# stm32f407ig_breakout.net
KiCad netlist of a schematic drawn in EAGLE
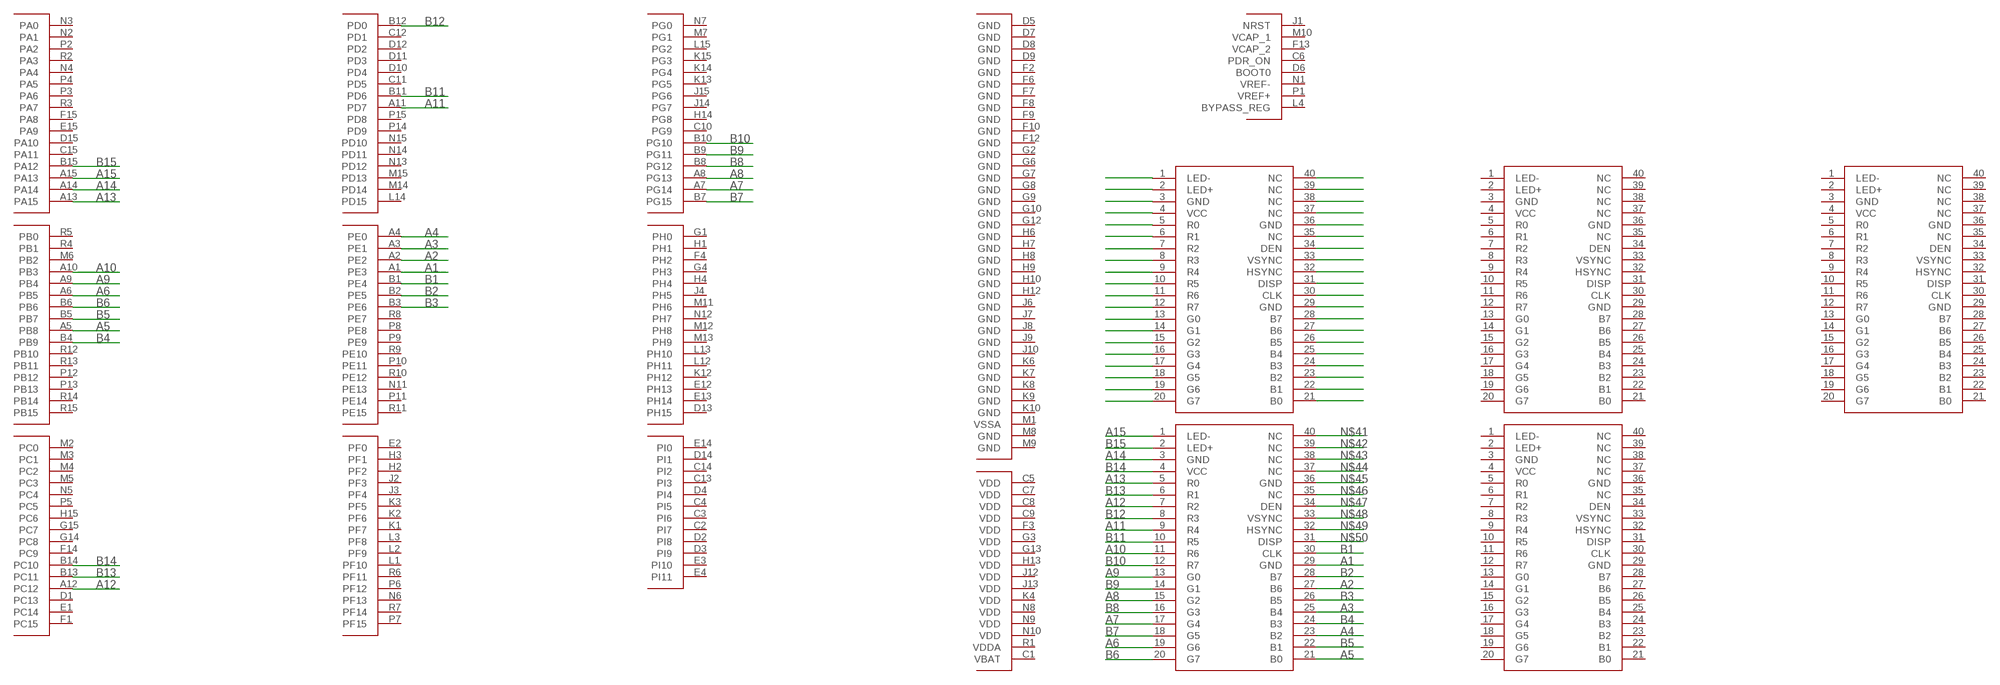
[diagram p0: schematic, sheet 1]

(export (version "E")
  (design (tool "Eeschema 10.0.6"))
  (components
    (comp (ref "TFT1")
      (value "MOLEX_CONNECTORS_SMD_NHD-4.3-480272EF-ATXL")
      (footprint "eagle-import:MOLEX_CONNECTORS_SMD_40-PIN_SMD")
      (libsource (lib "eagle-import") (part "MOLEX_CONNECTORS_SMD_NHD-4.3-480272EF-ATXL"))
    )
    (comp (ref "TFT2")
      (value "MOLEX_CONNECTORS_SMD_NHD-4.3-480272EF-ATXL")
      (footprint "eagle-import:MOLEX_CONNECTORS_SMD_40-PIN_SMD")
      (libsource (lib "eagle-import") (part "MOLEX_CONNECTORS_SMD_NHD-4.3-480272EF-ATXL"))
    )
    (comp (ref "TFT3")
      (value "MOLEX_CONNECTORS_SMD_NHD-4.3-480272EF-ATXL")
      (footprint "eagle-import:MOLEX_CONNECTORS_SMD_40-PIN_SMD")
      (libsource (lib "eagle-import") (part "MOLEX_CONNECTORS_SMD_NHD-4.3-480272EF-ATXL"))
    )
    (comp (ref "TFT4")
      (value "MOLEX_CONNECTORS_SMD_NHD-4.3-480272EF-ATXL")
      (footprint "eagle-import:MOLEX_CONNECTORS_SMD_40-PIN_SMD")
      (libsource (lib "eagle-import") (part "MOLEX_CONNECTORS_SMD_NHD-4.3-480272EF-ATXL"))
    )
    (comp (ref "TFT5")
      (value "MOLEX_CONNECTORS_SMD_NHD-4.3-480272EF-ATXL")
      (footprint "eagle-import:MOLEX_CONNECTORS_SMD_40-PIN_SMD")
      (libsource (lib "eagle-import") (part "MOLEX_CONNECTORS_SMD_NHD-4.3-480272EF-ATXL"))
    )
    (comp (ref "U$1")
      (value "STM32F407IG")
      (footprint "eagle-import:UFBGA176+25")
      (libsource (lib "eagle-import") (part "STM32F407IG"))
    )
  )
  (nets
    (net (code "1") (name "/A1") (class "Default")
      (node (ref "TFT4") (pin "29") (pinfunction "GND_29") (pintype "bidirectional"))
      (node (ref "U$1") (pin "A1") (pinfunction "PE3_A1") (pintype "bidirectional"))
    )
    (net (code "2") (name "/A2") (class "Default")
      (node (ref "TFT4") (pin "27") (pinfunction "B6_27") (pintype "bidirectional"))
      (node (ref "U$1") (pin "A2") (pinfunction "PE2_A2") (pintype "bidirectional"))
    )
    (net (code "3") (name "/A3") (class "Default")
      (node (ref "TFT4") (pin "25") (pinfunction "B4_25") (pintype "bidirectional"))
      (node (ref "U$1") (pin "A3") (pinfunction "PE1_A3") (pintype "bidirectional"))
    )
    (net (code "4") (name "/A4") (class "Default")
      (node (ref "TFT4") (pin "23") (pinfunction "B2_23") (pintype "bidirectional"))
      (node (ref "U$1") (pin "A4") (pinfunction "PE0_A4") (pintype "bidirectional"))
    )
    (net (code "5") (name "/A5") (class "Default")
      (node (ref "TFT4") (pin "21") (pinfunction "B0_21") (pintype "bidirectional"))
      (node (ref "U$1") (pin "A5") (pinfunction "PB8_A5") (pintype "bidirectional"))
    )
    (net (code "6") (name "/A6") (class "Default")
      (node (ref "TFT4") (pin "19") (pinfunction "G6_19") (pintype "bidirectional"))
      (node (ref "U$1") (pin "A6") (pinfunction "PB5_A6") (pintype "bidirectional"))
    )
    (net (code "7") (name "/A7") (class "Default")
      (node (ref "TFT4") (pin "17") (pinfunction "G4_17") (pintype "bidirectional"))
      (node (ref "U$1") (pin "A7") (pinfunction "PG14_A7") (pintype "bidirectional"))
    )
    (net (code "8") (name "/A8") (class "Default")
      (node (ref "TFT4") (pin "15") (pinfunction "G2_15") (pintype "bidirectional"))
      (node (ref "U$1") (pin "A8") (pinfunction "PG13_A8") (pintype "bidirectional"))
    )
    (net (code "9") (name "/A9") (class "Default")
      (node (ref "TFT4") (pin "13") (pinfunction "G0_13") (pintype "bidirectional"))
      (node (ref "U$1") (pin "A9") (pinfunction "PB4_A9") (pintype "bidirectional"))
    )
    (net (code "10") (name "/A10") (class "Default")
      (node (ref "TFT4") (pin "11") (pinfunction "R6_11") (pintype "bidirectional"))
      (node (ref "U$1") (pin "A10") (pinfunction "PB3_A10") (pintype "bidirectional"))
    )
    (net (code "11") (name "/A11") (class "Default")
      (node (ref "TFT4") (pin "9") (pinfunction "R4_9") (pintype "bidirectional"))
      (node (ref "U$1") (pin "A11") (pinfunction "PD7_A11") (pintype "bidirectional"))
    )
    (net (code "12") (name "/A12") (class "Default")
      (node (ref "TFT4") (pin "7") (pinfunction "R2_7") (pintype "bidirectional"))
      (node (ref "U$1") (pin "A12") (pinfunction "PC12_A12") (pintype "bidirectional"))
    )
    (net (code "13") (name "/A13") (class "Default")
      (node (ref "TFT4") (pin "5") (pinfunction "R0_5") (pintype "bidirectional"))
      (node (ref "U$1") (pin "A13") (pinfunction "PA15_A13") (pintype "bidirectional"))
    )
    (net (code "14") (name "/A14") (class "Default")
      (node (ref "TFT4") (pin "3") (pinfunction "GND_3") (pintype "bidirectional"))
      (node (ref "U$1") (pin "A14") (pinfunction "PA14_A14") (pintype "bidirectional"))
    )
    (net (code "15") (name "/A15") (class "Default")
      (node (ref "TFT4") (pin "1") (pinfunction "LED-_1") (pintype "bidirectional"))
      (node (ref "U$1") (pin "A15") (pinfunction "PA13_A15") (pintype "bidirectional"))
    )
    (net (code "16") (name "/B1") (class "Default")
      (node (ref "TFT4") (pin "30") (pinfunction "CLK_30") (pintype "bidirectional"))
      (node (ref "U$1") (pin "B1") (pinfunction "PE4_B1") (pintype "bidirectional"))
    )
    (net (code "17") (name "/B2") (class "Default")
      (node (ref "TFT4") (pin "28") (pinfunction "B7_28") (pintype "bidirectional"))
      (node (ref "U$1") (pin "B2") (pinfunction "PE5_B2") (pintype "bidirectional"))
    )
    (net (code "18") (name "/B3") (class "Default")
      (node (ref "TFT4") (pin "26") (pinfunction "B5_26") (pintype "bidirectional"))
      (node (ref "U$1") (pin "B3") (pinfunction "PE6_B3") (pintype "bidirectional"))
    )
    (net (code "19") (name "/B4") (class "Default")
      (node (ref "TFT4") (pin "24") (pinfunction "B3_24") (pintype "bidirectional"))
      (node (ref "U$1") (pin "B4") (pinfunction "PB9_B4") (pintype "bidirectional"))
    )
    (net (code "20") (name "/B5") (class "Default")
      (node (ref "TFT4") (pin "22") (pinfunction "B1_22") (pintype "bidirectional"))
      (node (ref "U$1") (pin "B5") (pinfunction "PB7_B5") (pintype "bidirectional"))
    )
    (net (code "21") (name "/B6") (class "Default")
      (node (ref "TFT4") (pin "20") (pinfunction "G7_20") (pintype "bidirectional"))
      (node (ref "U$1") (pin "B6") (pinfunction "PB6_B6") (pintype "bidirectional"))
    )
    (net (code "22") (name "/B7") (class "Default")
      (node (ref "TFT4") (pin "18") (pinfunction "G5_18") (pintype "bidirectional"))
      (node (ref "U$1") (pin "B7") (pinfunction "PG15_B7") (pintype "bidirectional"))
    )
    (net (code "23") (name "/B8") (class "Default")
      (node (ref "TFT4") (pin "16") (pinfunction "G3_16") (pintype "bidirectional"))
      (node (ref "U$1") (pin "B8") (pinfunction "PG12_B8") (pintype "bidirectional"))
    )
    (net (code "24") (name "/B9") (class "Default")
      (node (ref "TFT4") (pin "14") (pinfunction "G1_14") (pintype "bidirectional"))
      (node (ref "U$1") (pin "B9") (pinfunction "PG11_B9") (pintype "bidirectional"))
    )
    (net (code "25") (name "/B10") (class "Default")
      (node (ref "TFT4") (pin "12") (pinfunction "R7_12") (pintype "bidirectional"))
      (node (ref "U$1") (pin "B10") (pinfunction "PG10_B10") (pintype "bidirectional"))
    )
    (net (code "26") (name "/B11") (class "Default")
      (node (ref "TFT4") (pin "10") (pinfunction "R5_10") (pintype "bidirectional"))
      (node (ref "U$1") (pin "B11") (pinfunction "PD6_B11") (pintype "bidirectional"))
    )
    (net (code "27") (name "/B12") (class "Default")
      (node (ref "TFT4") (pin "8") (pinfunction "R3_8") (pintype "bidirectional"))
      (node (ref "U$1") (pin "B12") (pinfunction "PD0_B12") (pintype "bidirectional"))
    )
    (net (code "28") (name "/B13") (class "Default")
      (node (ref "TFT4") (pin "6") (pinfunction "R1_6") (pintype "bidirectional"))
      (node (ref "U$1") (pin "B13") (pinfunction "PC11_B13") (pintype "bidirectional"))
    )
    (net (code "29") (name "/B14") (class "Default")
      (node (ref "TFT4") (pin "4") (pinfunction "VCC_4") (pintype "bidirectional"))
      (node (ref "U$1") (pin "B14") (pinfunction "PC10_B14") (pintype "bidirectional"))
    )
    (net (code "30") (name "/B15") (class "Default")
      (node (ref "TFT4") (pin "2") (pinfunction "LED+_2") (pintype "bidirectional"))
      (node (ref "U$1") (pin "B15") (pinfunction "PA12_B15") (pintype "bidirectional"))
    )
    (net (code "31") (name "/N$41") (class "Default")
      (node (ref "TFT4") (pin "40") (pinfunction "NC_40") (pintype "bidirectional"))
    )
    (net (code "32") (name "/N$42") (class "Default")
      (node (ref "TFT4") (pin "39") (pinfunction "NC_39") (pintype "bidirectional"))
    )
    (net (code "33") (name "/N$43") (class "Default")
      (node (ref "TFT4") (pin "38") (pinfunction "NC_38") (pintype "bidirectional"))
    )
    (net (code "34") (name "/N$44") (class "Default")
      (node (ref "TFT4") (pin "37") (pinfunction "NC_37") (pintype "bidirectional"))
    )
    (net (code "35") (name "/N$45") (class "Default")
      (node (ref "TFT4") (pin "36") (pinfunction "GND_36") (pintype "bidirectional"))
    )
    (net (code "36") (name "/N$46") (class "Default")
      (node (ref "TFT4") (pin "35") (pinfunction "NC_35") (pintype "bidirectional"))
    )
    (net (code "37") (name "/N$47") (class "Default")
      (node (ref "TFT4") (pin "34") (pinfunction "DEN_34") (pintype "bidirectional"))
    )
    (net (code "38") (name "/N$48") (class "Default")
      (node (ref "TFT4") (pin "33") (pinfunction "VSYNC_33") (pintype "bidirectional"))
    )
    (net (code "39") (name "/N$49") (class "Default")
      (node (ref "TFT4") (pin "32") (pinfunction "HSYNC_32") (pintype "bidirectional"))
    )
    (net (code "40") (name "/N$50") (class "Default")
      (node (ref "TFT4") (pin "31") (pinfunction "DISP_31") (pintype "bidirectional"))
    )
    (net (code "41") (name "unconnected-(TFT1-B0-Pad21)") (class "Default")
      (node (ref "TFT1") (pin "21") (pinfunction "B0_21") (pintype "bidirectional"))
    )
    (net (code "42") (name "unconnected-(TFT1-B1-Pad22)") (class "Default")
      (node (ref "TFT1") (pin "22") (pinfunction "B1_22") (pintype "bidirectional"))
    )
    (net (code "43") (name "unconnected-(TFT1-B2-Pad23)") (class "Default")
      (node (ref "TFT1") (pin "23") (pinfunction "B2_23") (pintype "bidirectional"))
    )
    (net (code "44") (name "unconnected-(TFT1-B3-Pad24)") (class "Default")
      (node (ref "TFT1") (pin "24") (pinfunction "B3_24") (pintype "bidirectional"))
    )
    (net (code "45") (name "unconnected-(TFT1-B4-Pad25)") (class "Default")
      (node (ref "TFT1") (pin "25") (pinfunction "B4_25") (pintype "bidirectional"))
    )
    (net (code "46") (name "unconnected-(TFT1-B5-Pad26)") (class "Default")
      (node (ref "TFT1") (pin "26") (pinfunction "B5_26") (pintype "bidirectional"))
    )
    (net (code "47") (name "unconnected-(TFT1-B6-Pad27)") (class "Default")
      (node (ref "TFT1") (pin "27") (pinfunction "B6_27") (pintype "bidirectional"))
    )
    (net (code "48") (name "unconnected-(TFT1-B7-Pad28)") (class "Default")
      (node (ref "TFT1") (pin "28") (pinfunction "B7_28") (pintype "bidirectional"))
    )
    (net (code "49") (name "unconnected-(TFT1-CLK-Pad30)") (class "Default")
      (node (ref "TFT1") (pin "30") (pinfunction "CLK_30") (pintype "bidirectional"))
    )
    (net (code "50") (name "unconnected-(TFT1-DEN-Pad34)") (class "Default")
      (node (ref "TFT1") (pin "34") (pinfunction "DEN_34") (pintype "bidirectional"))
    )
    (net (code "51") (name "unconnected-(TFT1-DISP-Pad31)") (class "Default")
      (node (ref "TFT1") (pin "31") (pinfunction "DISP_31") (pintype "bidirectional"))
    )
    (net (code "52") (name "unconnected-(TFT1-G0-Pad13)") (class "Default")
      (node (ref "TFT1") (pin "13") (pinfunction "G0_13") (pintype "bidirectional"))
    )
    (net (code "53") (name "unconnected-(TFT1-G1-Pad14)") (class "Default")
      (node (ref "TFT1") (pin "14") (pinfunction "G1_14") (pintype "bidirectional"))
    )
    (net (code "54") (name "unconnected-(TFT1-G2-Pad15)") (class "Default")
      (node (ref "TFT1") (pin "15") (pinfunction "G2_15") (pintype "bidirectional"))
    )
    (net (code "55") (name "unconnected-(TFT1-G3-Pad16)") (class "Default")
      (node (ref "TFT1") (pin "16") (pinfunction "G3_16") (pintype "bidirectional"))
    )
    (net (code "56") (name "unconnected-(TFT1-G4-Pad17)") (class "Default")
      (node (ref "TFT1") (pin "17") (pinfunction "G4_17") (pintype "bidirectional"))
    )
    (net (code "57") (name "unconnected-(TFT1-G5-Pad18)") (class "Default")
      (node (ref "TFT1") (pin "18") (pinfunction "G5_18") (pintype "bidirectional"))
    )
    (net (code "58") (name "unconnected-(TFT1-G6-Pad19)") (class "Default")
      (node (ref "TFT1") (pin "19") (pinfunction "G6_19") (pintype "bidirectional"))
    )
    (net (code "59") (name "unconnected-(TFT1-G7-Pad20)") (class "Default")
      (node (ref "TFT1") (pin "20") (pinfunction "G7_20") (pintype "bidirectional"))
    )
    (net (code "60") (name "unconnected-(TFT1-GND-Pad3)") (class "Default")
      (node (ref "TFT1") (pin "3") (pinfunction "GND_3") (pintype "bidirectional"))
    )
    (net (code "61") (name "unconnected-(TFT1-GND-Pad29)") (class "Default")
      (node (ref "TFT1") (pin "29") (pinfunction "GND_29") (pintype "bidirectional"))
    )
    (net (code "62") (name "unconnected-(TFT1-GND-Pad36)") (class "Default")
      (node (ref "TFT1") (pin "36") (pinfunction "GND_36") (pintype "bidirectional"))
    )
    (net (code "63") (name "unconnected-(TFT1-HSYNC-Pad32)") (class "Default")
      (node (ref "TFT1") (pin "32") (pinfunction "HSYNC_32") (pintype "bidirectional"))
    )
    (net (code "64") (name "unconnected-(TFT1-LED+-Pad2)") (class "Default")
      (node (ref "TFT1") (pin "2") (pinfunction "LED+_2") (pintype "bidirectional"))
    )
    (net (code "65") (name "unconnected-(TFT1-LED--Pad1)") (class "Default")
      (node (ref "TFT1") (pin "1") (pinfunction "LED-_1") (pintype "bidirectional"))
    )
    (net (code "66") (name "unconnected-(TFT1-NC-Pad35)") (class "Default")
      (node (ref "TFT1") (pin "35") (pinfunction "NC_35") (pintype "bidirectional"))
    )
    (net (code "67") (name "unconnected-(TFT1-NC-Pad37)") (class "Default")
      (node (ref "TFT1") (pin "37") (pinfunction "NC_37") (pintype "bidirectional"))
    )
    (net (code "68") (name "unconnected-(TFT1-NC-Pad38)") (class "Default")
      (node (ref "TFT1") (pin "38") (pinfunction "NC_38") (pintype "bidirectional"))
    )
    (net (code "69") (name "unconnected-(TFT1-NC-Pad39)") (class "Default")
      (node (ref "TFT1") (pin "39") (pinfunction "NC_39") (pintype "bidirectional"))
    )
    (net (code "70") (name "unconnected-(TFT1-NC-Pad40)") (class "Default")
      (node (ref "TFT1") (pin "40") (pinfunction "NC_40") (pintype "bidirectional"))
    )
    (net (code "71") (name "unconnected-(TFT1-R0-Pad5)") (class "Default")
      (node (ref "TFT1") (pin "5") (pinfunction "R0_5") (pintype "bidirectional"))
    )
    (net (code "72") (name "unconnected-(TFT1-R1-Pad6)") (class "Default")
      (node (ref "TFT1") (pin "6") (pinfunction "R1_6") (pintype "bidirectional"))
    )
    (net (code "73") (name "unconnected-(TFT1-R2-Pad7)") (class "Default")
      (node (ref "TFT1") (pin "7") (pinfunction "R2_7") (pintype "bidirectional"))
    )
    (net (code "74") (name "unconnected-(TFT1-R3-Pad8)") (class "Default")
      (node (ref "TFT1") (pin "8") (pinfunction "R3_8") (pintype "bidirectional"))
    )
    (net (code "75") (name "unconnected-(TFT1-R4-Pad9)") (class "Default")
      (node (ref "TFT1") (pin "9") (pinfunction "R4_9") (pintype "bidirectional"))
    )
    (net (code "76") (name "unconnected-(TFT1-R5-Pad10)") (class "Default")
      (node (ref "TFT1") (pin "10") (pinfunction "R5_10") (pintype "bidirectional"))
    )
    (net (code "77") (name "unconnected-(TFT1-R6-Pad11)") (class "Default")
      (node (ref "TFT1") (pin "11") (pinfunction "R6_11") (pintype "bidirectional"))
    )
    (net (code "78") (name "unconnected-(TFT1-R7-Pad12)") (class "Default")
      (node (ref "TFT1") (pin "12") (pinfunction "R7_12") (pintype "bidirectional"))
    )
    (net (code "79") (name "unconnected-(TFT1-VCC-Pad4)") (class "Default")
      (node (ref "TFT1") (pin "4") (pinfunction "VCC_4") (pintype "bidirectional"))
    )
    (net (code "80") (name "unconnected-(TFT1-VSYNC-Pad33)") (class "Default")
      (node (ref "TFT1") (pin "33") (pinfunction "VSYNC_33") (pintype "bidirectional"))
    )
    (net (code "81") (name "unconnected-(TFT2-B0-Pad21)") (class "Default")
      (node (ref "TFT2") (pin "21") (pinfunction "B0_21") (pintype "bidirectional"))
    )
    (net (code "82") (name "unconnected-(TFT2-B1-Pad22)") (class "Default")
      (node (ref "TFT2") (pin "22") (pinfunction "B1_22") (pintype "bidirectional"))
    )
    (net (code "83") (name "unconnected-(TFT2-B2-Pad23)") (class "Default")
      (node (ref "TFT2") (pin "23") (pinfunction "B2_23") (pintype "bidirectional"))
    )
    (net (code "84") (name "unconnected-(TFT2-B3-Pad24)") (class "Default")
      (node (ref "TFT2") (pin "24") (pinfunction "B3_24") (pintype "bidirectional"))
    )
    (net (code "85") (name "unconnected-(TFT2-B4-Pad25)") (class "Default")
      (node (ref "TFT2") (pin "25") (pinfunction "B4_25") (pintype "bidirectional"))
    )
    (net (code "86") (name "unconnected-(TFT2-B5-Pad26)") (class "Default")
      (node (ref "TFT2") (pin "26") (pinfunction "B5_26") (pintype "bidirectional"))
    )
    (net (code "87") (name "unconnected-(TFT2-B6-Pad27)") (class "Default")
      (node (ref "TFT2") (pin "27") (pinfunction "B6_27") (pintype "bidirectional"))
    )
    (net (code "88") (name "unconnected-(TFT2-B7-Pad28)") (class "Default")
      (node (ref "TFT2") (pin "28") (pinfunction "B7_28") (pintype "bidirectional"))
    )
    (net (code "89") (name "unconnected-(TFT2-CLK-Pad30)") (class "Default")
      (node (ref "TFT2") (pin "30") (pinfunction "CLK_30") (pintype "bidirectional"))
    )
    (net (code "90") (name "unconnected-(TFT2-DEN-Pad34)") (class "Default")
      (node (ref "TFT2") (pin "34") (pinfunction "DEN_34") (pintype "bidirectional"))
    )
    (net (code "91") (name "unconnected-(TFT2-DISP-Pad31)") (class "Default")
      (node (ref "TFT2") (pin "31") (pinfunction "DISP_31") (pintype "bidirectional"))
    )
    (net (code "92") (name "unconnected-(TFT2-G0-Pad13)") (class "Default")
      (node (ref "TFT2") (pin "13") (pinfunction "G0_13") (pintype "bidirectional"))
    )
    (net (code "93") (name "unconnected-(TFT2-G1-Pad14)") (class "Default")
      (node (ref "TFT2") (pin "14") (pinfunction "G1_14") (pintype "bidirectional"))
    )
    (net (code "94") (name "unconnected-(TFT2-G2-Pad15)") (class "Default")
      (node (ref "TFT2") (pin "15") (pinfunction "G2_15") (pintype "bidirectional"))
    )
    (net (code "95") (name "unconnected-(TFT2-G3-Pad16)") (class "Default")
      (node (ref "TFT2") (pin "16") (pinfunction "G3_16") (pintype "bidirectional"))
    )
    (net (code "96") (name "unconnected-(TFT2-G4-Pad17)") (class "Default")
      (node (ref "TFT2") (pin "17") (pinfunction "G4_17") (pintype "bidirectional"))
    )
    (net (code "97") (name "unconnected-(TFT2-G5-Pad18)") (class "Default")
      (node (ref "TFT2") (pin "18") (pinfunction "G5_18") (pintype "bidirectional"))
    )
    (net (code "98") (name "unconnected-(TFT2-G6-Pad19)") (class "Default")
      (node (ref "TFT2") (pin "19") (pinfunction "G6_19") (pintype "bidirectional"))
    )
    (net (code "99") (name "unconnected-(TFT2-G7-Pad20)") (class "Default")
      (node (ref "TFT2") (pin "20") (pinfunction "G7_20") (pintype "bidirectional"))
    )
    (net (code "100") (name "unconnected-(TFT2-GND-Pad3)") (class "Default")
      (node (ref "TFT2") (pin "3") (pinfunction "GND_3") (pintype "bidirectional"))
    )
    (net (code "101") (name "unconnected-(TFT2-GND-Pad29)") (class "Default")
      (node (ref "TFT2") (pin "29") (pinfunction "GND_29") (pintype "bidirectional"))
    )
    (net (code "102") (name "unconnected-(TFT2-GND-Pad36)") (class "Default")
      (node (ref "TFT2") (pin "36") (pinfunction "GND_36") (pintype "bidirectional"))
    )
    (net (code "103") (name "unconnected-(TFT2-HSYNC-Pad32)") (class "Default")
      (node (ref "TFT2") (pin "32") (pinfunction "HSYNC_32") (pintype "bidirectional"))
    )
    (net (code "104") (name "unconnected-(TFT2-LED+-Pad2)") (class "Default")
      (node (ref "TFT2") (pin "2") (pinfunction "LED+_2") (pintype "bidirectional"))
    )
    (net (code "105") (name "unconnected-(TFT2-LED--Pad1)") (class "Default")
      (node (ref "TFT2") (pin "1") (pinfunction "LED-_1") (pintype "bidirectional"))
    )
    (net (code "106") (name "unconnected-(TFT2-NC-Pad35)") (class "Default")
      (node (ref "TFT2") (pin "35") (pinfunction "NC_35") (pintype "bidirectional"))
    )
    (net (code "107") (name "unconnected-(TFT2-NC-Pad37)") (class "Default")
      (node (ref "TFT2") (pin "37") (pinfunction "NC_37") (pintype "bidirectional"))
    )
    (net (code "108") (name "unconnected-(TFT2-NC-Pad38)") (class "Default")
      (node (ref "TFT2") (pin "38") (pinfunction "NC_38") (pintype "bidirectional"))
    )
    (net (code "109") (name "unconnected-(TFT2-NC-Pad39)") (class "Default")
      (node (ref "TFT2") (pin "39") (pinfunction "NC_39") (pintype "bidirectional"))
    )
    (net (code "110") (name "unconnected-(TFT2-NC-Pad40)") (class "Default")
      (node (ref "TFT2") (pin "40") (pinfunction "NC_40") (pintype "bidirectional"))
    )
    (net (code "111") (name "unconnected-(TFT2-R0-Pad5)") (class "Default")
      (node (ref "TFT2") (pin "5") (pinfunction "R0_5") (pintype "bidirectional"))
    )
    (net (code "112") (name "unconnected-(TFT2-R1-Pad6)") (class "Default")
      (node (ref "TFT2") (pin "6") (pinfunction "R1_6") (pintype "bidirectional"))
    )
    (net (code "113") (name "unconnected-(TFT2-R2-Pad7)") (class "Default")
      (node (ref "TFT2") (pin "7") (pinfunction "R2_7") (pintype "bidirectional"))
    )
    (net (code "114") (name "unconnected-(TFT2-R3-Pad8)") (class "Default")
      (node (ref "TFT2") (pin "8") (pinfunction "R3_8") (pintype "bidirectional"))
    )
    (net (code "115") (name "unconnected-(TFT2-R4-Pad9)") (class "Default")
      (node (ref "TFT2") (pin "9") (pinfunction "R4_9") (pintype "bidirectional"))
    )
    (net (code "116") (name "unconnected-(TFT2-R5-Pad10)") (class "Default")
      (node (ref "TFT2") (pin "10") (pinfunction "R5_10") (pintype "bidirectional"))
    )
    (net (code "117") (name "unconnected-(TFT2-R6-Pad11)") (class "Default")
      (node (ref "TFT2") (pin "11") (pinfunction "R6_11") (pintype "bidirectional"))
    )
    (net (code "118") (name "unconnected-(TFT2-R7-Pad12)") (class "Default")
      (node (ref "TFT2") (pin "12") (pinfunction "R7_12") (pintype "bidirectional"))
    )
    (net (code "119") (name "unconnected-(TFT2-VCC-Pad4)") (class "Default")
      (node (ref "TFT2") (pin "4") (pinfunction "VCC_4") (pintype "bidirectional"))
    )
    (net (code "120") (name "unconnected-(TFT2-VSYNC-Pad33)") (class "Default")
      (node (ref "TFT2") (pin "33") (pinfunction "VSYNC_33") (pintype "bidirectional"))
    )
    (net (code "121") (name "unconnected-(TFT3-B0-Pad21)") (class "Default")
      (node (ref "TFT3") (pin "21") (pinfunction "B0_21") (pintype "bidirectional"))
    )
    (net (code "122") (name "unconnected-(TFT3-B1-Pad22)") (class "Default")
      (node (ref "TFT3") (pin "22") (pinfunction "B1_22") (pintype "bidirectional"))
    )
    (net (code "123") (name "unconnected-(TFT3-B2-Pad23)") (class "Default")
      (node (ref "TFT3") (pin "23") (pinfunction "B2_23") (pintype "bidirectional"))
    )
    (net (code "124") (name "unconnected-(TFT3-B3-Pad24)") (class "Default")
      (node (ref "TFT3") (pin "24") (pinfunction "B3_24") (pintype "bidirectional"))
    )
    (net (code "125") (name "unconnected-(TFT3-B4-Pad25)") (class "Default")
      (node (ref "TFT3") (pin "25") (pinfunction "B4_25") (pintype "bidirectional"))
    )
    (net (code "126") (name "unconnected-(TFT3-B5-Pad26)") (class "Default")
      (node (ref "TFT3") (pin "26") (pinfunction "B5_26") (pintype "bidirectional"))
    )
    (net (code "127") (name "unconnected-(TFT3-B6-Pad27)") (class "Default")
      (node (ref "TFT3") (pin "27") (pinfunction "B6_27") (pintype "bidirectional"))
    )
    (net (code "128") (name "unconnected-(TFT3-B7-Pad28)") (class "Default")
      (node (ref "TFT3") (pin "28") (pinfunction "B7_28") (pintype "bidirectional"))
    )
    (net (code "129") (name "unconnected-(TFT3-CLK-Pad30)") (class "Default")
      (node (ref "TFT3") (pin "30") (pinfunction "CLK_30") (pintype "bidirectional"))
    )
    (net (code "130") (name "unconnected-(TFT3-DEN-Pad34)") (class "Default")
      (node (ref "TFT3") (pin "34") (pinfunction "DEN_34") (pintype "bidirectional"))
    )
    (net (code "131") (name "unconnected-(TFT3-DISP-Pad31)") (class "Default")
      (node (ref "TFT3") (pin "31") (pinfunction "DISP_31") (pintype "bidirectional"))
    )
    (net (code "132") (name "unconnected-(TFT3-G0-Pad13)") (class "Default")
      (node (ref "TFT3") (pin "13") (pinfunction "G0_13") (pintype "bidirectional"))
    )
    (net (code "133") (name "unconnected-(TFT3-G1-Pad14)") (class "Default")
      (node (ref "TFT3") (pin "14") (pinfunction "G1_14") (pintype "bidirectional"))
    )
    (net (code "134") (name "unconnected-(TFT3-G2-Pad15)") (class "Default")
      (node (ref "TFT3") (pin "15") (pinfunction "G2_15") (pintype "bidirectional"))
    )
    (net (code "135") (name "unconnected-(TFT3-G3-Pad16)") (class "Default")
      (node (ref "TFT3") (pin "16") (pinfunction "G3_16") (pintype "bidirectional"))
    )
    (net (code "136") (name "unconnected-(TFT3-G4-Pad17)") (class "Default")
      (node (ref "TFT3") (pin "17") (pinfunction "G4_17") (pintype "bidirectional"))
    )
    (net (code "137") (name "unconnected-(TFT3-G5-Pad18)") (class "Default")
      (node (ref "TFT3") (pin "18") (pinfunction "G5_18") (pintype "bidirectional"))
    )
    (net (code "138") (name "unconnected-(TFT3-G6-Pad19)") (class "Default")
      (node (ref "TFT3") (pin "19") (pinfunction "G6_19") (pintype "bidirectional"))
    )
    (net (code "139") (name "unconnected-(TFT3-G7-Pad20)") (class "Default")
      (node (ref "TFT3") (pin "20") (pinfunction "G7_20") (pintype "bidirectional"))
    )
    (net (code "140") (name "unconnected-(TFT3-GND-Pad3)") (class "Default")
      (node (ref "TFT3") (pin "3") (pinfunction "GND_3") (pintype "bidirectional"))
    )
    (net (code "141") (name "unconnected-(TFT3-GND-Pad29)") (class "Default")
      (node (ref "TFT3") (pin "29") (pinfunction "GND_29") (pintype "bidirectional"))
    )
    (net (code "142") (name "unconnected-(TFT3-GND-Pad36)") (class "Default")
      (node (ref "TFT3") (pin "36") (pinfunction "GND_36") (pintype "bidirectional"))
    )
    (net (code "143") (name "unconnected-(TFT3-HSYNC-Pad32)") (class "Default")
      (node (ref "TFT3") (pin "32") (pinfunction "HSYNC_32") (pintype "bidirectional"))
    )
    (net (code "144") (name "unconnected-(TFT3-LED+-Pad2)") (class "Default")
      (node (ref "TFT3") (pin "2") (pinfunction "LED+_2") (pintype "bidirectional"))
    )
    (net (code "145") (name "unconnected-(TFT3-LED--Pad1)") (class "Default")
      (node (ref "TFT3") (pin "1") (pinfunction "LED-_1") (pintype "bidirectional"))
    )
    (net (code "146") (name "unconnected-(TFT3-NC-Pad35)") (class "Default")
      (node (ref "TFT3") (pin "35") (pinfunction "NC_35") (pintype "bidirectional"))
    )
    (net (code "147") (name "unconnected-(TFT3-NC-Pad37)") (class "Default")
      (node (ref "TFT3") (pin "37") (pinfunction "NC_37") (pintype "bidirectional"))
    )
    (net (code "148") (name "unconnected-(TFT3-NC-Pad38)") (class "Default")
      (node (ref "TFT3") (pin "38") (pinfunction "NC_38") (pintype "bidirectional"))
    )
    (net (code "149") (name "unconnected-(TFT3-NC-Pad39)") (class "Default")
      (node (ref "TFT3") (pin "39") (pinfunction "NC_39") (pintype "bidirectional"))
    )
    (net (code "150") (name "unconnected-(TFT3-NC-Pad40)") (class "Default")
      (node (ref "TFT3") (pin "40") (pinfunction "NC_40") (pintype "bidirectional"))
    )
    (net (code "151") (name "unconnected-(TFT3-R0-Pad5)") (class "Default")
      (node (ref "TFT3") (pin "5") (pinfunction "R0_5") (pintype "bidirectional"))
    )
    (net (code "152") (name "unconnected-(TFT3-R1-Pad6)") (class "Default")
      (node (ref "TFT3") (pin "6") (pinfunction "R1_6") (pintype "bidirectional"))
    )
    (net (code "153") (name "unconnected-(TFT3-R2-Pad7)") (class "Default")
      (node (ref "TFT3") (pin "7") (pinfunction "R2_7") (pintype "bidirectional"))
    )
    (net (code "154") (name "unconnected-(TFT3-R3-Pad8)") (class "Default")
      (node (ref "TFT3") (pin "8") (pinfunction "R3_8") (pintype "bidirectional"))
    )
    (net (code "155") (name "unconnected-(TFT3-R4-Pad9)") (class "Default")
      (node (ref "TFT3") (pin "9") (pinfunction "R4_9") (pintype "bidirectional"))
    )
    (net (code "156") (name "unconnected-(TFT3-R5-Pad10)") (class "Default")
      (node (ref "TFT3") (pin "10") (pinfunction "R5_10") (pintype "bidirectional"))
    )
    (net (code "157") (name "unconnected-(TFT3-R6-Pad11)") (class "Default")
      (node (ref "TFT3") (pin "11") (pinfunction "R6_11") (pintype "bidirectional"))
    )
    (net (code "158") (name "unconnected-(TFT3-R7-Pad12)") (class "Default")
      (node (ref "TFT3") (pin "12") (pinfunction "R7_12") (pintype "bidirectional"))
    )
    (net (code "159") (name "unconnected-(TFT3-VCC-Pad4)") (class "Default")
      (node (ref "TFT3") (pin "4") (pinfunction "VCC_4") (pintype "bidirectional"))
    )
    (net (code "160") (name "unconnected-(TFT3-VSYNC-Pad33)") (class "Default")
      (node (ref "TFT3") (pin "33") (pinfunction "VSYNC_33") (pintype "bidirectional"))
    )
    (net (code "161") (name "unconnected-(TFT5-B0-Pad21)") (class "Default")
      (node (ref "TFT5") (pin "21") (pinfunction "B0_21") (pintype "bidirectional"))
    )
    (net (code "162") (name "unconnected-(TFT5-B1-Pad22)") (class "Default")
      (node (ref "TFT5") (pin "22") (pinfunction "B1_22") (pintype "bidirectional"))
    )
    (net (code "163") (name "unconnected-(TFT5-B2-Pad23)") (class "Default")
      (node (ref "TFT5") (pin "23") (pinfunction "B2_23") (pintype "bidirectional"))
    )
    (net (code "164") (name "unconnected-(TFT5-B3-Pad24)") (class "Default")
      (node (ref "TFT5") (pin "24") (pinfunction "B3_24") (pintype "bidirectional"))
    )
    (net (code "165") (name "unconnected-(TFT5-B4-Pad25)") (class "Default")
      (node (ref "TFT5") (pin "25") (pinfunction "B4_25") (pintype "bidirectional"))
    )
    (net (code "166") (name "unconnected-(TFT5-B5-Pad26)") (class "Default")
      (node (ref "TFT5") (pin "26") (pinfunction "B5_26") (pintype "bidirectional"))
    )
    (net (code "167") (name "unconnected-(TFT5-B6-Pad27)") (class "Default")
      (node (ref "TFT5") (pin "27") (pinfunction "B6_27") (pintype "bidirectional"))
    )
    (net (code "168") (name "unconnected-(TFT5-B7-Pad28)") (class "Default")
      (node (ref "TFT5") (pin "28") (pinfunction "B7_28") (pintype "bidirectional"))
    )
    (net (code "169") (name "unconnected-(TFT5-CLK-Pad30)") (class "Default")
      (node (ref "TFT5") (pin "30") (pinfunction "CLK_30") (pintype "bidirectional"))
    )
    (net (code "170") (name "unconnected-(TFT5-DEN-Pad34)") (class "Default")
      (node (ref "TFT5") (pin "34") (pinfunction "DEN_34") (pintype "bidirectional"))
    )
    (net (code "171") (name "unconnected-(TFT5-DISP-Pad31)") (class "Default")
      (node (ref "TFT5") (pin "31") (pinfunction "DISP_31") (pintype "bidirectional"))
    )
    (net (code "172") (name "unconnected-(TFT5-G0-Pad13)") (class "Default")
      (node (ref "TFT5") (pin "13") (pinfunction "G0_13") (pintype "bidirectional"))
    )
    (net (code "173") (name "unconnected-(TFT5-G1-Pad14)") (class "Default")
      (node (ref "TFT5") (pin "14") (pinfunction "G1_14") (pintype "bidirectional"))
    )
    (net (code "174") (name "unconnected-(TFT5-G2-Pad15)") (class "Default")
      (node (ref "TFT5") (pin "15") (pinfunction "G2_15") (pintype "bidirectional"))
    )
    (net (code "175") (name "unconnected-(TFT5-G3-Pad16)") (class "Default")
      (node (ref "TFT5") (pin "16") (pinfunction "G3_16") (pintype "bidirectional"))
    )
    (net (code "176") (name "unconnected-(TFT5-G4-Pad17)") (class "Default")
      (node (ref "TFT5") (pin "17") (pinfunction "G4_17") (pintype "bidirectional"))
    )
    (net (code "177") (name "unconnected-(TFT5-G5-Pad18)") (class "Default")
      (node (ref "TFT5") (pin "18") (pinfunction "G5_18") (pintype "bidirectional"))
    )
    (net (code "178") (name "unconnected-(TFT5-G6-Pad19)") (class "Default")
      (node (ref "TFT5") (pin "19") (pinfunction "G6_19") (pintype "bidirectional"))
    )
    (net (code "179") (name "unconnected-(TFT5-G7-Pad20)") (class "Default")
      (node (ref "TFT5") (pin "20") (pinfunction "G7_20") (pintype "bidirectional"))
    )
    (net (code "180") (name "unconnected-(TFT5-GND-Pad3)") (class "Default")
      (node (ref "TFT5") (pin "3") (pinfunction "GND_3") (pintype "bidirectional"))
    )
    (net (code "181") (name "unconnected-(TFT5-GND-Pad29)") (class "Default")
      (node (ref "TFT5") (pin "29") (pinfunction "GND_29") (pintype "bidirectional"))
    )
    (net (code "182") (name "unconnected-(TFT5-GND-Pad36)") (class "Default")
      (node (ref "TFT5") (pin "36") (pinfunction "GND_36") (pintype "bidirectional"))
    )
    (net (code "183") (name "unconnected-(TFT5-HSYNC-Pad32)") (class "Default")
      (node (ref "TFT5") (pin "32") (pinfunction "HSYNC_32") (pintype "bidirectional"))
    )
    (net (code "184") (name "unconnected-(TFT5-LED+-Pad2)") (class "Default")
      (node (ref "TFT5") (pin "2") (pinfunction "LED+_2") (pintype "bidirectional"))
    )
    (net (code "185") (name "unconnected-(TFT5-LED--Pad1)") (class "Default")
      (node (ref "TFT5") (pin "1") (pinfunction "LED-_1") (pintype "bidirectional"))
    )
    (net (code "186") (name "unconnected-(TFT5-NC-Pad35)") (class "Default")
      (node (ref "TFT5") (pin "35") (pinfunction "NC_35") (pintype "bidirectional"))
    )
    (net (code "187") (name "unconnected-(TFT5-NC-Pad37)") (class "Default")
      (node (ref "TFT5") (pin "37") (pinfunction "NC_37") (pintype "bidirectional"))
    )
    (net (code "188") (name "unconnected-(TFT5-NC-Pad38)") (class "Default")
      (node (ref "TFT5") (pin "38") (pinfunction "NC_38") (pintype "bidirectional"))
    )
    (net (code "189") (name "unconnected-(TFT5-NC-Pad39)") (class "Default")
      (node (ref "TFT5") (pin "39") (pinfunction "NC_39") (pintype "bidirectional"))
    )
    (net (code "190") (name "unconnected-(TFT5-NC-Pad40)") (class "Default")
      (node (ref "TFT5") (pin "40") (pinfunction "NC_40") (pintype "bidirectional"))
    )
    (net (code "191") (name "unconnected-(TFT5-R0-Pad5)") (class "Default")
      (node (ref "TFT5") (pin "5") (pinfunction "R0_5") (pintype "bidirectional"))
    )
    (net (code "192") (name "unconnected-(TFT5-R1-Pad6)") (class "Default")
      (node (ref "TFT5") (pin "6") (pinfunction "R1_6") (pintype "bidirectional"))
    )
    (net (code "193") (name "unconnected-(TFT5-R2-Pad7)") (class "Default")
      (node (ref "TFT5") (pin "7") (pinfunction "R2_7") (pintype "bidirectional"))
    )
    (net (code "194") (name "unconnected-(TFT5-R3-Pad8)") (class "Default")
      (node (ref "TFT5") (pin "8") (pinfunction "R3_8") (pintype "bidirectional"))
    )
    (net (code "195") (name "unconnected-(TFT5-R4-Pad9)") (class "Default")
      (node (ref "TFT5") (pin "9") (pinfunction "R4_9") (pintype "bidirectional"))
    )
    (net (code "196") (name "unconnected-(TFT5-R5-Pad10)") (class "Default")
      (node (ref "TFT5") (pin "10") (pinfunction "R5_10") (pintype "bidirectional"))
    )
    (net (code "197") (name "unconnected-(TFT5-R6-Pad11)") (class "Default")
      (node (ref "TFT5") (pin "11") (pinfunction "R6_11") (pintype "bidirectional"))
    )
    (net (code "198") (name "unconnected-(TFT5-R7-Pad12)") (class "Default")
      (node (ref "TFT5") (pin "12") (pinfunction "R7_12") (pintype "bidirectional"))
    )
    (net (code "199") (name "unconnected-(TFT5-VCC-Pad4)") (class "Default")
      (node (ref "TFT5") (pin "4") (pinfunction "VCC_4") (pintype "bidirectional"))
    )
    (net (code "200") (name "unconnected-(TFT5-VSYNC-Pad33)") (class "Default")
      (node (ref "TFT5") (pin "33") (pinfunction "VSYNC_33") (pintype "bidirectional"))
    )
    (net (code "201") (name "unconnected-(U$1-BOOT0-PadD6)") (class "Default")
      (node (ref "U$1") (pin "D6") (pinfunction "BOOT0_D6") (pintype "bidirectional"))
    )
    (net (code "202") (name "unconnected-(U$1-BYPASS_REG-PadL4)") (class "Default")
      (node (ref "U$1") (pin "L4") (pinfunction "BYPASS_REG_L4") (pintype "bidirectional"))
    )
    (net (code "203") (name "unconnected-(U$1-GND-PadD5)") (class "Default")
      (node (ref "U$1") (pin "D5") (pinfunction "GND_D5") (pintype "bidirectional"))
    )
    (net (code "204") (name "unconnected-(U$1-GND-PadD7)") (class "Default")
      (node (ref "U$1") (pin "D7") (pinfunction "GND_D7") (pintype "bidirectional"))
    )
    (net (code "205") (name "unconnected-(U$1-GND-PadD8)") (class "Default")
      (node (ref "U$1") (pin "D8") (pinfunction "GND_D8") (pintype "bidirectional"))
    )
    (net (code "206") (name "unconnected-(U$1-GND-PadD9)") (class "Default")
      (node (ref "U$1") (pin "D9") (pinfunction "GND_D9") (pintype "bidirectional"))
    )
    (net (code "207") (name "unconnected-(U$1-GND-PadF2)") (class "Default")
      (node (ref "U$1") (pin "F2") (pinfunction "GND_F2") (pintype "bidirectional"))
    )
    (net (code "208") (name "unconnected-(U$1-GND-PadF6)") (class "Default")
      (node (ref "U$1") (pin "F6") (pinfunction "GND_F6") (pintype "bidirectional"))
    )
    (net (code "209") (name "unconnected-(U$1-GND-PadF7)") (class "Default")
      (node (ref "U$1") (pin "F7") (pinfunction "GND_F7") (pintype "bidirectional"))
    )
    (net (code "210") (name "unconnected-(U$1-GND-PadF8)") (class "Default")
      (node (ref "U$1") (pin "F8") (pinfunction "GND_F8") (pintype "bidirectional"))
    )
    (net (code "211") (name "unconnected-(U$1-GND-PadF9)") (class "Default")
      (node (ref "U$1") (pin "F9") (pinfunction "GND_F9") (pintype "bidirectional"))
    )
    (net (code "212") (name "unconnected-(U$1-GND-PadF10)") (class "Default")
      (node (ref "U$1") (pin "F10") (pinfunction "GND_F10") (pintype "bidirectional"))
    )
    (net (code "213") (name "unconnected-(U$1-GND-PadF12)") (class "Default")
      (node (ref "U$1") (pin "F12") (pinfunction "GND_F12") (pintype "bidirectional"))
    )
    (net (code "214") (name "unconnected-(U$1-GND-PadG2)") (class "Default")
      (node (ref "U$1") (pin "G2") (pinfunction "GND_G2") (pintype "bidirectional"))
    )
    (net (code "215") (name "unconnected-(U$1-GND-PadG6)") (class "Default")
      (node (ref "U$1") (pin "G6") (pinfunction "GND_G6") (pintype "bidirectional"))
    )
    (net (code "216") (name "unconnected-(U$1-GND-PadG7)") (class "Default")
      (node (ref "U$1") (pin "G7") (pinfunction "GND_G7") (pintype "bidirectional"))
    )
    (net (code "217") (name "unconnected-(U$1-GND-PadG8)") (class "Default")
      (node (ref "U$1") (pin "G8") (pinfunction "GND_G8") (pintype "bidirectional"))
    )
    (net (code "218") (name "unconnected-(U$1-GND-PadG9)") (class "Default")
      (node (ref "U$1") (pin "G9") (pinfunction "GND_G9") (pintype "bidirectional"))
    )
    (net (code "219") (name "unconnected-(U$1-GND-PadG10)") (class "Default")
      (node (ref "U$1") (pin "G10") (pinfunction "GND_G10") (pintype "bidirectional"))
    )
    (net (code "220") (name "unconnected-(U$1-GND-PadG12)") (class "Default")
      (node (ref "U$1") (pin "G12") (pinfunction "GND_G12") (pintype "bidirectional"))
    )
    (net (code "221") (name "unconnected-(U$1-GND-PadH6)") (class "Default")
      (node (ref "U$1") (pin "H6") (pinfunction "GND_H6") (pintype "bidirectional"))
    )
    (net (code "222") (name "unconnected-(U$1-GND-PadH7)") (class "Default")
      (node (ref "U$1") (pin "H7") (pinfunction "GND_H7") (pintype "bidirectional"))
    )
    (net (code "223") (name "unconnected-(U$1-GND-PadH8)") (class "Default")
      (node (ref "U$1") (pin "H8") (pinfunction "GND_H8") (pintype "bidirectional"))
    )
    (net (code "224") (name "unconnected-(U$1-GND-PadH9)") (class "Default")
      (node (ref "U$1") (pin "H9") (pinfunction "GND_H9") (pintype "bidirectional"))
    )
    (net (code "225") (name "unconnected-(U$1-GND-PadH10)") (class "Default")
      (node (ref "U$1") (pin "H10") (pinfunction "GND_H10") (pintype "bidirectional"))
    )
    (net (code "226") (name "unconnected-(U$1-GND-PadH12)") (class "Default")
      (node (ref "U$1") (pin "H12") (pinfunction "GND_H12") (pintype "bidirectional"))
    )
    (net (code "227") (name "unconnected-(U$1-GND-PadJ6)") (class "Default")
      (node (ref "U$1") (pin "J6") (pinfunction "GND_J6") (pintype "bidirectional"))
    )
    (net (code "228") (name "unconnected-(U$1-GND-PadJ7)") (class "Default")
      (node (ref "U$1") (pin "J7") (pinfunction "GND_J7") (pintype "bidirectional"))
    )
    (net (code "229") (name "unconnected-(U$1-GND-PadJ8)") (class "Default")
      (node (ref "U$1") (pin "J8") (pinfunction "GND_J8") (pintype "bidirectional"))
    )
    (net (code "230") (name "unconnected-(U$1-GND-PadJ9)") (class "Default")
      (node (ref "U$1") (pin "J9") (pinfunction "GND_J9") (pintype "bidirectional"))
    )
    (net (code "231") (name "unconnected-(U$1-GND-PadJ10)") (class "Default")
      (node (ref "U$1") (pin "J10") (pinfunction "GND_J10") (pintype "bidirectional"))
    )
    (net (code "232") (name "unconnected-(U$1-GND-PadK6)") (class "Default")
      (node (ref "U$1") (pin "K6") (pinfunction "GND_K6") (pintype "bidirectional"))
    )
    (net (code "233") (name "unconnected-(U$1-GND-PadK7)") (class "Default")
      (node (ref "U$1") (pin "K7") (pinfunction "GND_K7") (pintype "bidirectional"))
    )
    (net (code "234") (name "unconnected-(U$1-GND-PadK8)") (class "Default")
      (node (ref "U$1") (pin "K8") (pinfunction "GND_K8") (pintype "bidirectional"))
    )
    (net (code "235") (name "unconnected-(U$1-GND-PadK9)") (class "Default")
      (node (ref "U$1") (pin "K9") (pinfunction "GND_K9") (pintype "bidirectional"))
    )
    (net (code "236") (name "unconnected-(U$1-GND-PadK10)") (class "Default")
      (node (ref "U$1") (pin "K10") (pinfunction "GND_K10") (pintype "bidirectional"))
    )
    (net (code "237") (name "unconnected-(U$1-GND-PadM8)") (class "Default")
      (node (ref "U$1") (pin "M8") (pinfunction "GND_M8") (pintype "bidirectional"))
    )
    (net (code "238") (name "unconnected-(U$1-GND-PadM9)") (class "Default")
      (node (ref "U$1") (pin "M9") (pinfunction "GND_M9") (pintype "bidirectional"))
    )
    (net (code "239") (name "unconnected-(U$1-NRST-PadJ1)") (class "Default")
      (node (ref "U$1") (pin "J1") (pinfunction "NRST_J1") (pintype "bidirectional"))
    )
    (net (code "240") (name "unconnected-(U$1-PA0-PadN3)") (class "Default")
      (node (ref "U$1") (pin "N3") (pinfunction "PA0_N3") (pintype "bidirectional"))
    )
    (net (code "241") (name "unconnected-(U$1-PA1-PadN2)") (class "Default")
      (node (ref "U$1") (pin "N2") (pinfunction "PA1_N2") (pintype "bidirectional"))
    )
    (net (code "242") (name "unconnected-(U$1-PA2-PadP2)") (class "Default")
      (node (ref "U$1") (pin "P2") (pinfunction "PA2_P2") (pintype "bidirectional"))
    )
    (net (code "243") (name "unconnected-(U$1-PA3-PadR2)") (class "Default")
      (node (ref "U$1") (pin "R2") (pinfunction "PA3_R2") (pintype "bidirectional"))
    )
    (net (code "244") (name "unconnected-(U$1-PA4-PadN4)") (class "Default")
      (node (ref "U$1") (pin "N4") (pinfunction "PA4_N4") (pintype "bidirectional"))
    )
    (net (code "245") (name "unconnected-(U$1-PA5-PadP4)") (class "Default")
      (node (ref "U$1") (pin "P4") (pinfunction "PA5_P4") (pintype "bidirectional"))
    )
    (net (code "246") (name "unconnected-(U$1-PA6-PadP3)") (class "Default")
      (node (ref "U$1") (pin "P3") (pinfunction "PA6_P3") (pintype "bidirectional"))
    )
    (net (code "247") (name "unconnected-(U$1-PA7-PadR3)") (class "Default")
      (node (ref "U$1") (pin "R3") (pinfunction "PA7_R3") (pintype "bidirectional"))
    )
    (net (code "248") (name "unconnected-(U$1-PA8-PadF15)") (class "Default")
      (node (ref "U$1") (pin "F15") (pinfunction "PA8_F15") (pintype "bidirectional"))
    )
    (net (code "249") (name "unconnected-(U$1-PA9-PadE15)") (class "Default")
      (node (ref "U$1") (pin "E15") (pinfunction "PA9_E15") (pintype "bidirectional"))
    )
    (net (code "250") (name "unconnected-(U$1-PA10-PadD15)") (class "Default")
      (node (ref "U$1") (pin "D15") (pinfunction "PA10_D15") (pintype "bidirectional"))
    )
    (net (code "251") (name "unconnected-(U$1-PA11-PadC15)") (class "Default")
      (node (ref "U$1") (pin "C15") (pinfunction "PA11_C15") (pintype "bidirectional"))
    )
    (net (code "252") (name "unconnected-(U$1-PB0-PadR5)") (class "Default")
      (node (ref "U$1") (pin "R5") (pinfunction "PB0_R5") (pintype "bidirectional"))
    )
    (net (code "253") (name "unconnected-(U$1-PB1-PadR4)") (class "Default")
      (node (ref "U$1") (pin "R4") (pinfunction "PB1_R4") (pintype "bidirectional"))
    )
    (net (code "254") (name "unconnected-(U$1-PB2-PadM6)") (class "Default")
      (node (ref "U$1") (pin "M6") (pinfunction "PB2_M6") (pintype "bidirectional"))
    )
    (net (code "255") (name "unconnected-(U$1-PB10-PadR12)") (class "Default")
      (node (ref "U$1") (pin "R12") (pinfunction "PB10_R12") (pintype "bidirectional"))
    )
    (net (code "256") (name "unconnected-(U$1-PB11-PadR13)") (class "Default")
      (node (ref "U$1") (pin "R13") (pinfunction "PB11_R13") (pintype "bidirectional"))
    )
    (net (code "257") (name "unconnected-(U$1-PB12-PadP12)") (class "Default")
      (node (ref "U$1") (pin "P12") (pinfunction "PB12_P12") (pintype "bidirectional"))
    )
    (net (code "258") (name "unconnected-(U$1-PB13-PadP13)") (class "Default")
      (node (ref "U$1") (pin "P13") (pinfunction "PB13_P13") (pintype "bidirectional"))
    )
    (net (code "259") (name "unconnected-(U$1-PB14-PadR14)") (class "Default")
      (node (ref "U$1") (pin "R14") (pinfunction "PB14_R14") (pintype "bidirectional"))
    )
    (net (code "260") (name "unconnected-(U$1-PB15-PadR15)") (class "Default")
      (node (ref "U$1") (pin "R15") (pinfunction "PB15_R15") (pintype "bidirectional"))
    )
    (net (code "261") (name "unconnected-(U$1-PC0-PadM2)") (class "Default")
      (node (ref "U$1") (pin "M2") (pinfunction "PC0_M2") (pintype "bidirectional"))
    )
    (net (code "262") (name "unconnected-(U$1-PC1-PadM3)") (class "Default")
      (node (ref "U$1") (pin "M3") (pinfunction "PC1_M3") (pintype "bidirectional"))
    )
    (net (code "263") (name "unconnected-(U$1-PC2-PadM4)") (class "Default")
      (node (ref "U$1") (pin "M4") (pinfunction "PC2_M4") (pintype "bidirectional"))
    )
    (net (code "264") (name "unconnected-(U$1-PC3-PadM5)") (class "Default")
      (node (ref "U$1") (pin "M5") (pinfunction "PC3_M5") (pintype "bidirectional"))
    )
    (net (code "265") (name "unconnected-(U$1-PC4-PadN5)") (class "Default")
      (node (ref "U$1") (pin "N5") (pinfunction "PC4_N5") (pintype "bidirectional"))
    )
    (net (code "266") (name "unconnected-(U$1-PC5-PadP5)") (class "Default")
      (node (ref "U$1") (pin "P5") (pinfunction "PC5_P5") (pintype "bidirectional"))
    )
    (net (code "267") (name "unconnected-(U$1-PC6-PadH15)") (class "Default")
      (node (ref "U$1") (pin "H15") (pinfunction "PC6_H15") (pintype "bidirectional"))
    )
    (net (code "268") (name "unconnected-(U$1-PC7-PadG15)") (class "Default")
      (node (ref "U$1") (pin "G15") (pinfunction "PC7_G15") (pintype "bidirectional"))
    )
    (net (code "269") (name "unconnected-(U$1-PC8-PadG14)") (class "Default")
      (node (ref "U$1") (pin "G14") (pinfunction "PC8_G14") (pintype "bidirectional"))
    )
    (net (code "270") (name "unconnected-(U$1-PC9-PadF14)") (class "Default")
      (node (ref "U$1") (pin "F14") (pinfunction "PC9_F14") (pintype "bidirectional"))
    )
    (net (code "271") (name "unconnected-(U$1-PC13-PadD1)") (class "Default")
      (node (ref "U$1") (pin "D1") (pinfunction "PC13_D1") (pintype "bidirectional"))
    )
    (net (code "272") (name "unconnected-(U$1-PC14-PadE1)") (class "Default")
      (node (ref "U$1") (pin "E1") (pinfunction "PC14_E1") (pintype "bidirectional"))
    )
    (net (code "273") (name "unconnected-(U$1-PC15-PadF1)") (class "Default")
      (node (ref "U$1") (pin "F1") (pinfunction "PC15_F1") (pintype "bidirectional"))
    )
    (net (code "274") (name "unconnected-(U$1-PD1-PadC12)") (class "Default")
      (node (ref "U$1") (pin "C12") (pinfunction "PD1_C12") (pintype "bidirectional"))
    )
    (net (code "275") (name "unconnected-(U$1-PD2-PadD12)") (class "Default")
      (node (ref "U$1") (pin "D12") (pinfunction "PD2_D12") (pintype "bidirectional"))
    )
    (net (code "276") (name "unconnected-(U$1-PD3-PadD11)") (class "Default")
      (node (ref "U$1") (pin "D11") (pinfunction "PD3_D11") (pintype "bidirectional"))
    )
    (net (code "277") (name "unconnected-(U$1-PD4-PadD10)") (class "Default")
      (node (ref "U$1") (pin "D10") (pinfunction "PD4_D10") (pintype "bidirectional"))
    )
    (net (code "278") (name "unconnected-(U$1-PD5-PadC11)") (class "Default")
      (node (ref "U$1") (pin "C11") (pinfunction "PD5_C11") (pintype "bidirectional"))
    )
    (net (code "279") (name "unconnected-(U$1-PD8-PadP15)") (class "Default")
      (node (ref "U$1") (pin "P15") (pinfunction "PD8_P15") (pintype "bidirectional"))
    )
    (net (code "280") (name "unconnected-(U$1-PD9-PadP14)") (class "Default")
      (node (ref "U$1") (pin "P14") (pinfunction "PD9_P14") (pintype "bidirectional"))
    )
    (net (code "281") (name "unconnected-(U$1-PD10-PadN15)") (class "Default")
      (node (ref "U$1") (pin "N15") (pinfunction "PD10_N15") (pintype "bidirectional"))
    )
    (net (code "282") (name "unconnected-(U$1-PD11-PadN14)") (class "Default")
      (node (ref "U$1") (pin "N14") (pinfunction "PD11_N14") (pintype "bidirectional"))
    )
    (net (code "283") (name "unconnected-(U$1-PD12-PadN13)") (class "Default")
      (node (ref "U$1") (pin "N13") (pinfunction "PD12_N13") (pintype "bidirectional"))
    )
    (net (code "284") (name "unconnected-(U$1-PD13-PadM15)") (class "Default")
      (node (ref "U$1") (pin "M15") (pinfunction "PD13_M15") (pintype "bidirectional"))
    )
    (net (code "285") (name "unconnected-(U$1-PD14-PadM14)") (class "Default")
      (node (ref "U$1") (pin "M14") (pinfunction "PD14_M14") (pintype "bidirectional"))
    )
    (net (code "286") (name "unconnected-(U$1-PD15-PadL14)") (class "Default")
      (node (ref "U$1") (pin "L14") (pinfunction "PD15_L14") (pintype "bidirectional"))
    )
    (net (code "287") (name "unconnected-(U$1-PDR_ON-PadC6)") (class "Default")
      (node (ref "U$1") (pin "C6") (pinfunction "PDR_ON_C6") (pintype "bidirectional"))
    )
    (net (code "288") (name "unconnected-(U$1-PE7-PadR8)") (class "Default")
      (node (ref "U$1") (pin "R8") (pinfunction "PE7_R8") (pintype "bidirectional"))
    )
    (net (code "289") (name "unconnected-(U$1-PE8-PadP8)") (class "Default")
      (node (ref "U$1") (pin "P8") (pinfunction "PE8_P8") (pintype "bidirectional"))
    )
    (net (code "290") (name "unconnected-(U$1-PE9-PadP9)") (class "Default")
      (node (ref "U$1") (pin "P9") (pinfunction "PE9_P9") (pintype "bidirectional"))
    )
    (net (code "291") (name "unconnected-(U$1-PE10-PadR9)") (class "Default")
      (node (ref "U$1") (pin "R9") (pinfunction "PE10_R9") (pintype "bidirectional"))
    )
    (net (code "292") (name "unconnected-(U$1-PE11-PadP10)") (class "Default")
      (node (ref "U$1") (pin "P10") (pinfunction "PE11_P10") (pintype "bidirectional"))
    )
    (net (code "293") (name "unconnected-(U$1-PE12-PadR10)") (class "Default")
      (node (ref "U$1") (pin "R10") (pinfunction "PE12_R10") (pintype "bidirectional"))
    )
    (net (code "294") (name "unconnected-(U$1-PE13-PadN11)") (class "Default")
      (node (ref "U$1") (pin "N11") (pinfunction "PE13_N11") (pintype "bidirectional"))
    )
    (net (code "295") (name "unconnected-(U$1-PE14-PadP11)") (class "Default")
      (node (ref "U$1") (pin "P11") (pinfunction "PE14_P11") (pintype "bidirectional"))
    )
    (net (code "296") (name "unconnected-(U$1-PE15-PadR11)") (class "Default")
      (node (ref "U$1") (pin "R11") (pinfunction "PE15_R11") (pintype "bidirectional"))
    )
    (net (code "297") (name "unconnected-(U$1-PF0-PadE2)") (class "Default")
      (node (ref "U$1") (pin "E2") (pinfunction "PF0_E2") (pintype "bidirectional"))
    )
    (net (code "298") (name "unconnected-(U$1-PF1-PadH3)") (class "Default")
      (node (ref "U$1") (pin "H3") (pinfunction "PF1_H3") (pintype "bidirectional"))
    )
    (net (code "299") (name "unconnected-(U$1-PF2-PadH2)") (class "Default")
      (node (ref "U$1") (pin "H2") (pinfunction "PF2_H2") (pintype "bidirectional"))
    )
    (net (code "300") (name "unconnected-(U$1-PF3-PadJ2)") (class "Default")
      (node (ref "U$1") (pin "J2") (pinfunction "PF3_J2") (pintype "bidirectional"))
    )
    (net (code "301") (name "unconnected-(U$1-PF4-PadJ3)") (class "Default")
      (node (ref "U$1") (pin "J3") (pinfunction "PF4_J3") (pintype "bidirectional"))
    )
    (net (code "302") (name "unconnected-(U$1-PF5-PadK3)") (class "Default")
      (node (ref "U$1") (pin "K3") (pinfunction "PF5_K3") (pintype "bidirectional"))
    )
    (net (code "303") (name "unconnected-(U$1-PF6-PadK2)") (class "Default")
      (node (ref "U$1") (pin "K2") (pinfunction "PF6_K2") (pintype "bidirectional"))
    )
    (net (code "304") (name "unconnected-(U$1-PF7-PadK1)") (class "Default")
      (node (ref "U$1") (pin "K1") (pinfunction "PF7_K1") (pintype "bidirectional"))
    )
    (net (code "305") (name "unconnected-(U$1-PF8-PadL3)") (class "Default")
      (node (ref "U$1") (pin "L3") (pinfunction "PF8_L3") (pintype "bidirectional"))
    )
    (net (code "306") (name "unconnected-(U$1-PF9-PadL2)") (class "Default")
      (node (ref "U$1") (pin "L2") (pinfunction "PF9_L2") (pintype "bidirectional"))
    )
    (net (code "307") (name "unconnected-(U$1-PF10-PadL1)") (class "Default")
      (node (ref "U$1") (pin "L1") (pinfunction "PF10_L1") (pintype "bidirectional"))
    )
    (net (code "308") (name "unconnected-(U$1-PF11-PadR6)") (class "Default")
      (node (ref "U$1") (pin "R6") (pinfunction "PF11_R6") (pintype "bidirectional"))
    )
    (net (code "309") (name "unconnected-(U$1-PF12-PadP6)") (class "Default")
      (node (ref "U$1") (pin "P6") (pinfunction "PF12_P6") (pintype "bidirectional"))
    )
    (net (code "310") (name "unconnected-(U$1-PF13-PadN6)") (class "Default")
      (node (ref "U$1") (pin "N6") (pinfunction "PF13_N6") (pintype "bidirectional"))
    )
    (net (code "311") (name "unconnected-(U$1-PF14-PadR7)") (class "Default")
      (node (ref "U$1") (pin "R7") (pinfunction "PF14_R7") (pintype "bidirectional"))
    )
    (net (code "312") (name "unconnected-(U$1-PF15-PadP7)") (class "Default")
      (node (ref "U$1") (pin "P7") (pinfunction "PF15_P7") (pintype "bidirectional"))
    )
    (net (code "313") (name "unconnected-(U$1-PG0-PadN7)") (class "Default")
      (node (ref "U$1") (pin "N7") (pinfunction "PG0_N7") (pintype "bidirectional"))
    )
    (net (code "314") (name "unconnected-(U$1-PG1-PadM7)") (class "Default")
      (node (ref "U$1") (pin "M7") (pinfunction "PG1_M7") (pintype "bidirectional"))
    )
    (net (code "315") (name "unconnected-(U$1-PG2-PadL15)") (class "Default")
      (node (ref "U$1") (pin "L15") (pinfunction "PG2_L15") (pintype "bidirectional"))
    )
    (net (code "316") (name "unconnected-(U$1-PG3-PadK15)") (class "Default")
      (node (ref "U$1") (pin "K15") (pinfunction "PG3_K15") (pintype "bidirectional"))
    )
    (net (code "317") (name "unconnected-(U$1-PG4-PadK14)") (class "Default")
      (node (ref "U$1") (pin "K14") (pinfunction "PG4_K14") (pintype "bidirectional"))
    )
    (net (code "318") (name "unconnected-(U$1-PG5-PadK13)") (class "Default")
      (node (ref "U$1") (pin "K13") (pinfunction "PG5_K13") (pintype "bidirectional"))
    )
    (net (code "319") (name "unconnected-(U$1-PG6-PadJ15)") (class "Default")
      (node (ref "U$1") (pin "J15") (pinfunction "PG6_J15") (pintype "bidirectional"))
    )
    (net (code "320") (name "unconnected-(U$1-PG7-PadJ14)") (class "Default")
      (node (ref "U$1") (pin "J14") (pinfunction "PG7_J14") (pintype "bidirectional"))
    )
    (net (code "321") (name "unconnected-(U$1-PG8-PadH14)") (class "Default")
      (node (ref "U$1") (pin "H14") (pinfunction "PG8_H14") (pintype "bidirectional"))
    )
    (net (code "322") (name "unconnected-(U$1-PG9-PadC10)") (class "Default")
      (node (ref "U$1") (pin "C10") (pinfunction "PG9_C10") (pintype "bidirectional"))
    )
    (net (code "323") (name "unconnected-(U$1-PH0-PadG1)") (class "Default")
      (node (ref "U$1") (pin "G1") (pinfunction "PH0_G1") (pintype "bidirectional"))
    )
    (net (code "324") (name "unconnected-(U$1-PH1-PadH1)") (class "Default")
      (node (ref "U$1") (pin "H1") (pinfunction "PH1_H1") (pintype "bidirectional"))
    )
    (net (code "325") (name "unconnected-(U$1-PH2-PadF4)") (class "Default")
      (node (ref "U$1") (pin "F4") (pinfunction "PH2_F4") (pintype "bidirectional"))
    )
    (net (code "326") (name "unconnected-(U$1-PH3-PadG4)") (class "Default")
      (node (ref "U$1") (pin "G4") (pinfunction "PH3_G4") (pintype "bidirectional"))
    )
    (net (code "327") (name "unconnected-(U$1-PH4-PadH4)") (class "Default")
      (node (ref "U$1") (pin "H4") (pinfunction "PH4_H4") (pintype "bidirectional"))
    )
    (net (code "328") (name "unconnected-(U$1-PH5-PadJ4)") (class "Default")
      (node (ref "U$1") (pin "J4") (pinfunction "PH5_J4") (pintype "bidirectional"))
    )
    (net (code "329") (name "unconnected-(U$1-PH6-PadM11)") (class "Default")
      (node (ref "U$1") (pin "M11") (pinfunction "PH6_M11") (pintype "bidirectional"))
    )
    (net (code "330") (name "unconnected-(U$1-PH7-PadN12)") (class "Default")
      (node (ref "U$1") (pin "N12") (pinfunction "PH7_N12") (pintype "bidirectional"))
    )
    (net (code "331") (name "unconnected-(U$1-PH8-PadM12)") (class "Default")
      (node (ref "U$1") (pin "M12") (pinfunction "PH8_M12") (pintype "bidirectional"))
    )
    (net (code "332") (name "unconnected-(U$1-PH9-PadM13)") (class "Default")
      (node (ref "U$1") (pin "M13") (pinfunction "PH9_M13") (pintype "bidirectional"))
    )
    (net (code "333") (name "unconnected-(U$1-PH10-PadL13)") (class "Default")
      (node (ref "U$1") (pin "L13") (pinfunction "PH10_L13") (pintype "bidirectional"))
    )
    (net (code "334") (name "unconnected-(U$1-PH11-PadL12)") (class "Default")
      (node (ref "U$1") (pin "L12") (pinfunction "PH11_L12") (pintype "bidirectional"))
    )
    (net (code "335") (name "unconnected-(U$1-PH12-PadK12)") (class "Default")
      (node (ref "U$1") (pin "K12") (pinfunction "PH12_K12") (pintype "bidirectional"))
    )
    (net (code "336") (name "unconnected-(U$1-PH13-PadE12)") (class "Default")
      (node (ref "U$1") (pin "E12") (pinfunction "PH13_E12") (pintype "bidirectional"))
    )
    (net (code "337") (name "unconnected-(U$1-PH14-PadE13)") (class "Default")
      (node (ref "U$1") (pin "E13") (pinfunction "PH14_E13") (pintype "bidirectional"))
    )
    (net (code "338") (name "unconnected-(U$1-PH15-PadD13)") (class "Default")
      (node (ref "U$1") (pin "D13") (pinfunction "PH15_D13") (pintype "bidirectional"))
    )
    (net (code "339") (name "unconnected-(U$1-PI0-PadE14)") (class "Default")
      (node (ref "U$1") (pin "E14") (pinfunction "PI0_E14") (pintype "bidirectional"))
    )
    (net (code "340") (name "unconnected-(U$1-PI1-PadD14)") (class "Default")
      (node (ref "U$1") (pin "D14") (pinfunction "PI1_D14") (pintype "bidirectional"))
    )
    (net (code "341") (name "unconnected-(U$1-PI2-PadC14)") (class "Default")
      (node (ref "U$1") (pin "C14") (pinfunction "PI2_C14") (pintype "bidirectional"))
    )
    (net (code "342") (name "unconnected-(U$1-PI3-PadC13)") (class "Default")
      (node (ref "U$1") (pin "C13") (pinfunction "PI3_C13") (pintype "bidirectional"))
    )
    (net (code "343") (name "unconnected-(U$1-PI4-PadD4)") (class "Default")
      (node (ref "U$1") (pin "D4") (pinfunction "PI4_D4") (pintype "bidirectional"))
    )
    (net (code "344") (name "unconnected-(U$1-PI5-PadC4)") (class "Default")
      (node (ref "U$1") (pin "C4") (pinfunction "PI5_C4") (pintype "bidirectional"))
    )
    (net (code "345") (name "unconnected-(U$1-PI6-PadC3)") (class "Default")
      (node (ref "U$1") (pin "C3") (pinfunction "PI6_C3") (pintype "bidirectional"))
    )
    (net (code "346") (name "unconnected-(U$1-PI7-PadC2)") (class "Default")
      (node (ref "U$1") (pin "C2") (pinfunction "PI7_C2") (pintype "bidirectional"))
    )
    (net (code "347") (name "unconnected-(U$1-PI8-PadD2)") (class "Default")
      (node (ref "U$1") (pin "D2") (pinfunction "PI8_D2") (pintype "bidirectional"))
    )
    (net (code "348") (name "unconnected-(U$1-PI9-PadD3)") (class "Default")
      (node (ref "U$1") (pin "D3") (pinfunction "PI9_D3") (pintype "bidirectional"))
    )
    (net (code "349") (name "unconnected-(U$1-PI10-PadE3)") (class "Default")
      (node (ref "U$1") (pin "E3") (pinfunction "PI10_E3") (pintype "bidirectional"))
    )
    (net (code "350") (name "unconnected-(U$1-PI11-PadE4)") (class "Default")
      (node (ref "U$1") (pin "E4") (pinfunction "PI11_E4") (pintype "bidirectional"))
    )
    (net (code "351") (name "unconnected-(U$1-VBAT-PadC1)") (class "Default")
      (node (ref "U$1") (pin "C1") (pinfunction "VBAT_C1") (pintype "bidirectional"))
    )
    (net (code "352") (name "unconnected-(U$1-VCAP_1-PadM10)") (class "Default")
      (node (ref "U$1") (pin "M10") (pinfunction "VCAP_1_M10") (pintype "bidirectional"))
    )
    (net (code "353") (name "unconnected-(U$1-VCAP_2-PadF13)") (class "Default")
      (node (ref "U$1") (pin "F13") (pinfunction "VCAP_2_F13") (pintype "bidirectional"))
    )
    (net (code "354") (name "unconnected-(U$1-VDD-PadC5)") (class "Default")
      (node (ref "U$1") (pin "C5") (pinfunction "VDD_C5") (pintype "bidirectional"))
    )
    (net (code "355") (name "unconnected-(U$1-VDD-PadC7)") (class "Default")
      (node (ref "U$1") (pin "C7") (pinfunction "VDD_C7") (pintype "bidirectional"))
    )
    (net (code "356") (name "unconnected-(U$1-VDD-PadC8)") (class "Default")
      (node (ref "U$1") (pin "C8") (pinfunction "VDD_C8") (pintype "bidirectional"))
    )
    (net (code "357") (name "unconnected-(U$1-VDD-PadC9)") (class "Default")
      (node (ref "U$1") (pin "C9") (pinfunction "VDD_C9") (pintype "bidirectional"))
    )
    (net (code "358") (name "unconnected-(U$1-VDD-PadF3)") (class "Default")
      (node (ref "U$1") (pin "F3") (pinfunction "VDD_F3") (pintype "bidirectional"))
    )
    (net (code "359") (name "unconnected-(U$1-VDD-PadG3)") (class "Default")
      (node (ref "U$1") (pin "G3") (pinfunction "VDD_G3") (pintype "bidirectional"))
    )
    (net (code "360") (name "unconnected-(U$1-VDD-PadG13)") (class "Default")
      (node (ref "U$1") (pin "G13") (pinfunction "VDD_G13") (pintype "bidirectional"))
    )
    (net (code "361") (name "unconnected-(U$1-VDD-PadH13)") (class "Default")
      (node (ref "U$1") (pin "H13") (pinfunction "VDD_H13") (pintype "bidirectional"))
    )
    (net (code "362") (name "unconnected-(U$1-VDD-PadJ12)") (class "Default")
      (node (ref "U$1") (pin "J12") (pinfunction "VDD_J12") (pintype "bidirectional"))
    )
    (net (code "363") (name "unconnected-(U$1-VDD-PadJ13)") (class "Default")
      (node (ref "U$1") (pin "J13") (pinfunction "VDD_J13") (pintype "bidirectional"))
    )
    (net (code "364") (name "unconnected-(U$1-VDD-PadK4)") (class "Default")
      (node (ref "U$1") (pin "K4") (pinfunction "VDD_K4") (pintype "bidirectional"))
    )
    (net (code "365") (name "unconnected-(U$1-VDD-PadN8)") (class "Default")
      (node (ref "U$1") (pin "N8") (pinfunction "VDD_N8") (pintype "bidirectional"))
    )
    (net (code "366") (name "unconnected-(U$1-VDD-PadN9)") (class "Default")
      (node (ref "U$1") (pin "N9") (pinfunction "VDD_N9") (pintype "bidirectional"))
    )
    (net (code "367") (name "unconnected-(U$1-VDD-PadN10)") (class "Default")
      (node (ref "U$1") (pin "N10") (pinfunction "VDD_N10") (pintype "bidirectional"))
    )
    (net (code "368") (name "unconnected-(U$1-VDDA-PadR1)") (class "Default")
      (node (ref "U$1") (pin "R1") (pinfunction "VDDA_R1") (pintype "bidirectional"))
    )
    (net (code "369") (name "unconnected-(U$1-VREF+-PadP1)") (class "Default")
      (node (ref "U$1") (pin "P1") (pinfunction "VREF+_P1") (pintype "bidirectional"))
    )
    (net (code "370") (name "unconnected-(U$1-VREF--PadN1)") (class "Default")
      (node (ref "U$1") (pin "N1") (pinfunction "VREF-_N1") (pintype "bidirectional"))
    )
    (net (code "371") (name "unconnected-(U$1-VSSA-PadM1)") (class "Default")
      (node (ref "U$1") (pin "M1") (pinfunction "VSSA_M1") (pintype "bidirectional"))
    )
  )
)
